# ProtectionChannelB.net
KiCad netlist of a schematic drawn in Altium Designer
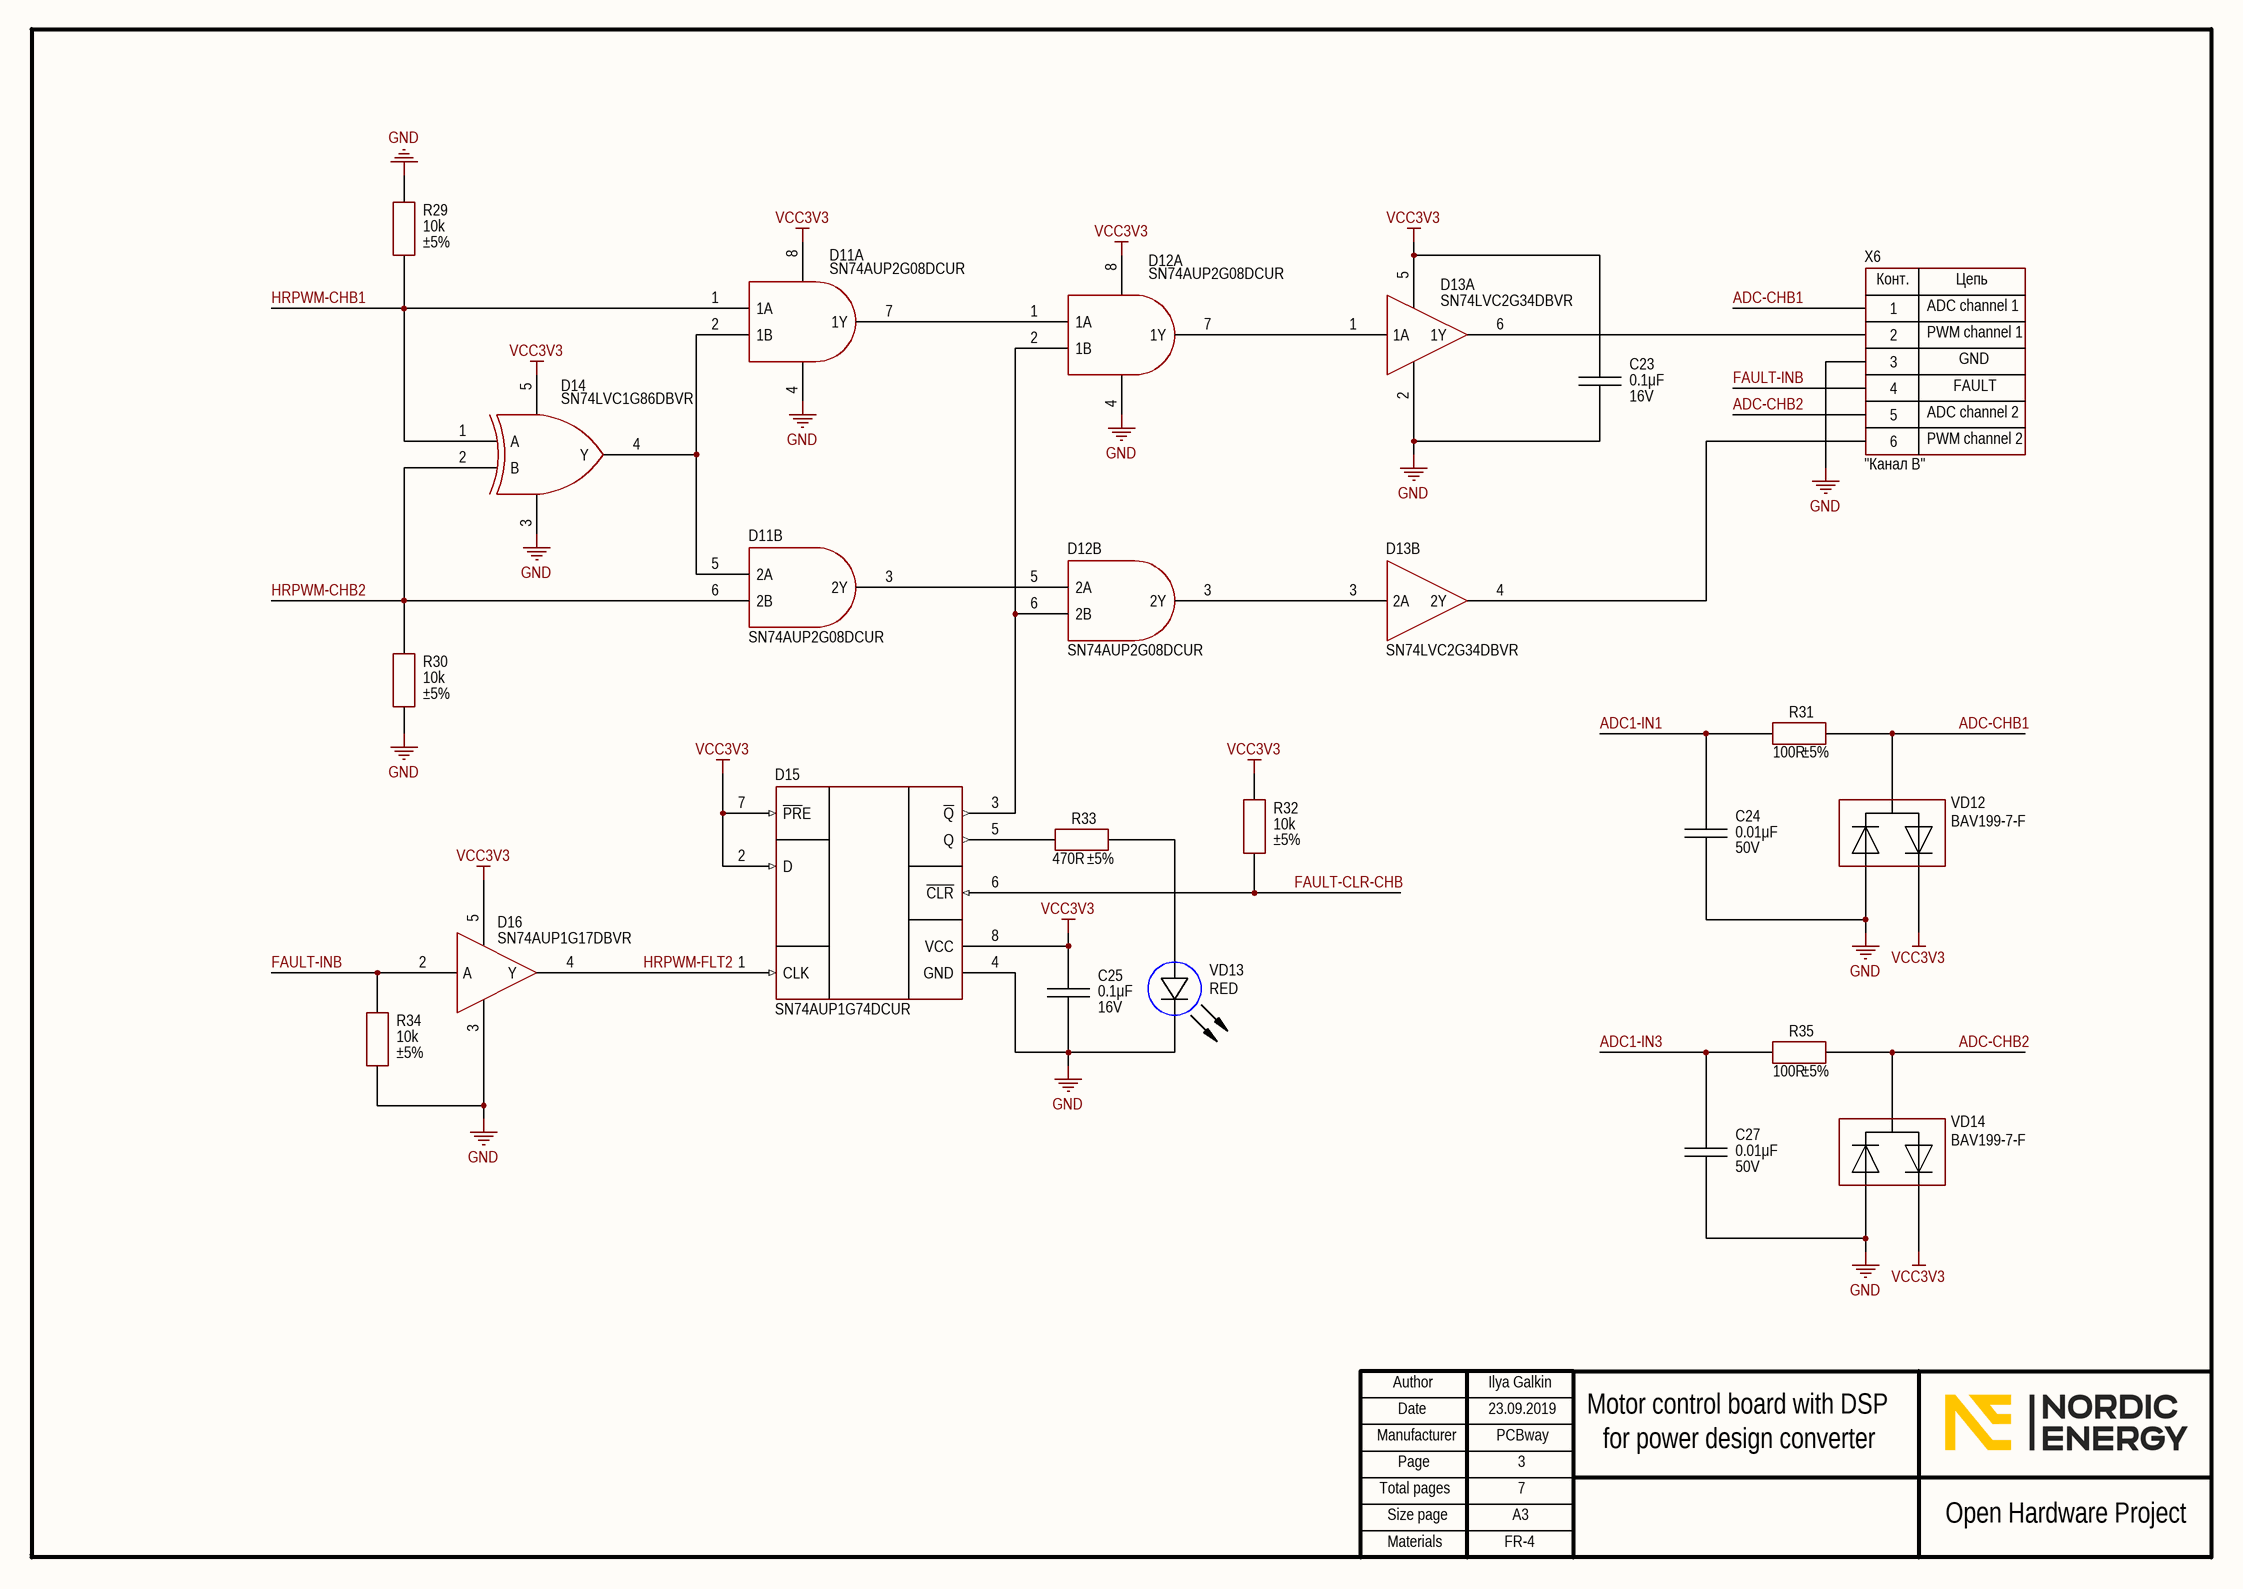
[diagram p0: ProtectionChannelB.SchDoc]

(export (version "E")
  (design (tool "Eeschema 10.0.6"))
  (components
    (comp (ref "C23")
      (value "0.1μF")
      (footprint "CAP: 0805")
      (fields
        (field (name "MANUFACTURER") "Yageo")
        (field (name "PARTNUMBER") "CC0805KRX7R7BB104")
        (field (name "VALUEMANUFACTURERPARTNUMBER") "Ceramic capacitor, 0.1μF, X7R, ±10%, 16V, 0805, -55...+125°C")
        (field (name "VOLTAGE") "16V")
      )
      (libsource (lib "Capacitor") (part "Ceramic_0805"))
    )
    (comp (ref "C24")
      (value "0.01μF")
      (footprint "CAP: 0805")
      (fields
        (field (name "MANUFACTURER") "Yageo")
        (field (name "PARTNUMBER") "CC0805KRX7R9BB103")
        (field (name "VALUEMANUFACTURERPARTNUMBER") "Ceramic capacitor, 0.01μF, X7R, ±10%, 50V, 0805, -55...+125°C")
        (field (name "VOLTAGE") "50V")
      )
      (libsource (lib "Capacitor") (part "Ceramic_0805"))
    )
    (comp (ref "C25")
      (value "0.1μF")
      (footprint "CAP: 0805")
      (fields
        (field (name "MANUFACTURER") "Yageo")
        (field (name "PARTNUMBER") "CC0805KRX7R7BB104")
        (field (name "VALUEMANUFACTURERPARTNUMBER") "Ceramic capacitor, 0.1μF, X7R, ±10%, 16V, 0805, -55...+125°C")
        (field (name "VOLTAGE") "16V")
      )
      (libsource (lib "Capacitor") (part "Ceramic_0805"))
    )
    (comp (ref "C27")
      (value "0.01μF")
      (footprint "CAP: 0805")
      (fields
        (field (name "MANUFACTURER") "Yageo")
        (field (name "PARTNUMBER") "CC0805KRX7R9BB103")
        (field (name "VALUEMANUFACTURERPARTNUMBER") "Ceramic capacitor, 0.01μF, X7R, ±10%, 50V, 0805, -55...+125°C")
        (field (name "VOLTAGE") "50V")
      )
      (libsource (lib "Capacitor") (part "Ceramic_0805"))
    )
    (comp (ref "D11")
      (value "~")
      (footprint "8-VSSOP")
      (description "AND")
      (fields
        (field (name "MANUFACTURER") "Texas Instruments")
        (field (name "VALUEMANUFACTURERPARTNUMBER") "IC logic AND, 0.8...3.6V, -40...+855°C, 8-VSSOP")
        (field (name "PARTNUMBER") "SN74AUP2G08DCUR")
      )
      (libsource (lib "IC. Logic") (part "SN74AUP2G08DCUR"))
    )
    (comp (ref "D12")
      (value "~")
      (footprint "8-VSSOP")
      (description "AND")
      (fields
        (field (name "MANUFACTURER") "Texas Instruments")
        (field (name "VALUEMANUFACTURERPARTNUMBER") "IC logic AND, 0.8...3.6V, -40...+855°C, 8-VSSOP")
        (field (name "PARTNUMBER") "SN74AUP2G08DCUR")
      )
      (libsource (lib "IC. Logic") (part "SN74AUP2G08DCUR"))
    )
    (comp (ref "D13")
      (value "~")
      (footprint "SOT23-6")
      (description "Buffer")
      (fields
        (field (name "MANUFACTURER") "Texas Instruments")
        (field (name "VALUEMANUFACTURERPARTNUMBER") "IC logic buffer, 1.65...5.5V, -40...+125°C, SOT23-6")
        (field (name "PARTNUMBER") "SN74LVC2G34DBVR")
      )
      (libsource (lib "IC. Logic") (part "SN74LVC2G34DBVR"))
    )
    (comp (ref "D14")
      (value "~")
      (footprint "SOT23-5")
      (description "XOR")
      (fields
        (field (name "MANUFACTURER") "Texas Instruments")
        (field (name "VALUEMANUFACTURERPARTNUMBER") "IC logic XOR, 1.65...5.5V, -40...+125°C, SOT23-5")
        (field (name "PARTNUMBER") "SN74LVC1G86DBVR")
      )
      (libsource (lib "IC. Logic") (part "SN74LVC1G86DBVR"))
    )
    (comp (ref "D15")
      (value "~")
      (footprint "8-VSSOP")
      (description "D-trigger")
      (fields
        (field (name "MANUFACTURER") "Texas Instruments")
        (field (name "VALUEMANUFACTURERPARTNUMBER") "ICtrigger D-type, 0.8...3.6V, -40...+85°C, 8-VSSOP")
        (field (name "PARTNUMBER") "SN74AUP1G74DCUR")
      )
      (libsource (lib "IC. Logic") (part "SN74AUP1G74DCUR"))
    )
    (comp (ref "D16")
      (value "~")
      (footprint "SOT23-5")
      (description "Schmitt trigger")
      (fields
        (field (name "MANUFACTURER") "Texas Instruments")
        (field (name "VALUEMANUFACTURERPARTNUMBER") "IC Schmitt trigger, 0.8...3.6V, -40...+85°C, SOT23-6")
        (field (name "PARTNUMBER") "SN74AUP1G17DBVR")
      )
      (libsource (lib "IC. Logic") (part "SN74AUP1G17DBVR"))
    )
    (comp (ref "R29")
      (value "10k")
      (footprint "RES: 0805")
      (fields
        (field (name "MANUFACTURER") "Yageo")
        (field (name "PARTNUMBER") "RC0805JR-0710KL")
        (field (name "VALUEMANUFACTURERPARTNUMBER") "Resistor film, 10k, ±5%, 0805, 0.125W, -55...+125°C")
        (field (name "TOLERANCE") "±5%")
      )
      (libsource (lib "") (part "Resistor_0805_1"))
    )
    (comp (ref "R30")
      (value "10k")
      (footprint "RES: 0805")
      (fields
        (field (name "MANUFACTURER") "Yageo")
        (field (name "PARTNUMBER") "RC0805JR-0710KL")
        (field (name "VALUEMANUFACTURERPARTNUMBER") "Resistor film, 10k, ±5%, 0805, 0.125W, -55...+125°C")
        (field (name "TOLERANCE") "±5%")
      )
      (libsource (lib "") (part "Resistor_0805_1"))
    )
    (comp (ref "R31")
      (value "100R")
      (footprint "RES: 0805")
      (fields
        (field (name "MANUFACTURER") "Yageo")
        (field (name "PARTNUMBER") "RC0805JR-07100RL")
        (field (name "VALUEMANUFACTURERPARTNUMBER") "Resistor film, 100R, ±5%, 0805, 0.125W, -55...+125°C")
        (field (name "TOLERANCE") "±5%")
      )
      (libsource (lib "Resistor") (part "Resistor_0805"))
    )
    (comp (ref "R32")
      (value "10k")
      (footprint "RES: 0805")
      (fields
        (field (name "MANUFACTURER") "Yageo")
        (field (name "PARTNUMBER") "RC0805JR-0710KL")
        (field (name "VALUEMANUFACTURERPARTNUMBER") "Resistor film, 10k, ±5%, 0805, 0.125W, -55...+125°C")
        (field (name "TOLERANCE") "±5%")
      )
      (libsource (lib "") (part "Resistor_0805_1"))
    )
    (comp (ref "R33")
      (value "470R")
      (footprint "RES: 0805")
      (fields
        (field (name "MANUFACTURER") "Yageo")
        (field (name "PARTNUMBER") "RC0805JR-07470RL")
        (field (name "VALUEMANUFACTURERPARTNUMBER") "Resistor film, 470R, ±5%, 0805, 0.125W, -55...+125°C")
        (field (name "TOLERANCE") "±5%")
      )
      (libsource (lib "") (part "Resistor_0805_2"))
    )
    (comp (ref "R34")
      (value "10k")
      (footprint "RES: 0805")
      (fields
        (field (name "MANUFACTURER") "Yageo")
        (field (name "PARTNUMBER") "RC0805JR-0710KL")
        (field (name "VALUEMANUFACTURERPARTNUMBER") "Resistor film, 10k, ±5%, 0805, 0.125W, -55...+125°C")
        (field (name "TOLERANCE") "±5%")
      )
      (libsource (lib "") (part "Resistor_0805_1"))
    )
    (comp (ref "R35")
      (value "100R")
      (footprint "RES: 0805")
      (fields
        (field (name "MANUFACTURER") "Yageo")
        (field (name "PARTNUMBER") "RC0805JR-07100RL")
        (field (name "VALUEMANUFACTURERPARTNUMBER") "Resistor film, 100R, ±5%, 0805, 0.125W, -55...+125°C")
        (field (name "TOLERANCE") "±5%")
      )
      (libsource (lib "Resistor") (part "Resistor_0805"))
    )
    (comp (ref "VD12")
      (value "~")
      (footprint "SOT23")
      (fields
        (field (name "MANUFACTURER") "Diodes Incorporated")
        (field (name "VALUEMANUFACTURERPARTNUMBER") "Diode array, 85V, 140mA, 1.1V, 3us, SOT-23, -65...+150°C")
        (field (name "VOLTAGE") "85V")
        (field (name "PARTNUMBER") "BAV199-7-F")
      )
      (libsource (lib "Diode") (part "Diode_array"))
    )
    (comp (ref "VD13")
      (value "~")
      (footprint "LED: 0805R")
      (fields
        (field (name "MANUFACTURER") "Wurth")
        (field (name "VALUEMANUFACTURERPARTNUMBER") "LED, 20mA, 2V, 0805, -55...+150°C")
        (field (name "PARTNUMBER") "150080RS75000")
        (field (name "COLOR") "RED")
      )
      (libsource (lib "Diode") (part "LED_single"))
    )
    (comp (ref "VD14")
      (value "~")
      (footprint "SOT23")
      (fields
        (field (name "MANUFACTURER") "Diodes Incorporated")
        (field (name "VALUEMANUFACTURERPARTNUMBER") "Diode array, 85V, 140mA, 1.1V, 3us, SOT-23, -65...+150°C")
        (field (name "VOLTAGE") "85V")
        (field (name "PARTNUMBER") "BAV199-7-F")
      )
      (libsource (lib "Diode") (part "Diode_array"))
    )
    (comp (ref "X6")
      (value "~")
      (footprint "CON: PLD-6")
      (fields
        (field (name "MANUFACTURER") "Connfly")
        (field (name "VALUEMANUFACTURERPARTNUMBER") "Connector, 6pin, 2.54mm, 500VAC, 3A")
        (field (name "PARTNUMBER") "PLD-6")
        (field (name "COMMENTTEXT") "\"Канал B\"")
      )
      (libsource (lib "Connector") (part "PLD-6"))
    )
  )
  (nets
    (net (code "1") (name "/ADC-CHB1") (class "Default")
      (node (ref "R31") (pin "2") (pinfunction "2_2") (pintype "passive"))
      (node (ref "VD12") (pin "3") (pinfunction "3_3") (pintype "passive"))
      (node (ref "X6") (pin "1") (pinfunction "1_1") (pintype "passive"))
    )
    (net (code "2") (name "/ADC-CHB2") (class "Default")
      (node (ref "R35") (pin "2") (pinfunction "2_2") (pintype "passive"))
      (node (ref "VD14") (pin "3") (pinfunction "3_3") (pintype "passive"))
      (node (ref "X6") (pin "5") (pinfunction "5_5") (pintype "power_in"))
    )
    (net (code "3") (name "/ADC1-IN1") (class "Default")
      (node (ref "C24") (pin "2") (pinfunction "2_2") (pintype "power_in"))
      (node (ref "R31") (pin "1") (pinfunction "1_1") (pintype "passive"))
    )
    (net (code "4") (name "/ADC1-IN3") (class "Default")
      (node (ref "C27") (pin "2") (pinfunction "2_2") (pintype "power_in"))
      (node (ref "R35") (pin "1") (pinfunction "1_1") (pintype "passive"))
    )
    (net (code "5") (name "/FAULT-CLR-CHB") (class "Default")
      (node (ref "D15") (pin "6") (pinfunction "~{CLR}_6") (pintype "input"))
      (node (ref "R32") (pin "2") (pinfunction "2_2") (pintype "passive"))
    )
    (net (code "6") (name "/FAULT-INB") (class "Default")
      (node (ref "D16") (pin "2") (pinfunction "A_2") (pintype "passive"))
      (node (ref "R34") (pin "1") (pinfunction "1_1") (pintype "passive"))
      (node (ref "X6") (pin "4") (pinfunction "4_4") (pintype "power_in"))
    )
    (net (code "7") (name "/HRPWM-CHB1") (class "Default")
      (node (ref "D11") (pin "1") (pinfunction "1A_1") (pintype "passive"))
      (node (ref "D14") (pin "1") (pinfunction "A_1") (pintype "passive"))
      (node (ref "R29") (pin "2") (pinfunction "2_2") (pintype "passive"))
    )
    (net (code "8") (name "/HRPWM-CHB2") (class "Default")
      (node (ref "D11") (pin "6") (pinfunction "2B_6") (pintype "passive"))
      (node (ref "D14") (pin "2") (pinfunction "B_2") (pintype "passive"))
      (node (ref "R30") (pin "1") (pinfunction "1_1") (pintype "passive"))
    )
    (net (code "9") (name "/HRPWM-FLT2") (class "Default")
      (node (ref "D15") (pin "1") (pinfunction "CLK_1") (pintype "input"))
      (node (ref "D16") (pin "4") (pinfunction "Y_4") (pintype "passive"))
    )
    (net (code "10") (name "GND") (class "Default")
      (node (ref "C23") (pin "1") (pinfunction "1_1") (pintype "power_in"))
      (node (ref "C24") (pin "1") (pinfunction "1_1") (pintype "power_in"))
      (node (ref "C25") (pin "1") (pinfunction "1_1") (pintype "power_in"))
      (node (ref "C27") (pin "1") (pinfunction "1_1") (pintype "power_in"))
      (node (ref "D11") (pin "4") (pintype "passive"))
      (node (ref "D12") (pin "4") (pintype "passive"))
      (node (ref "D13") (pin "2") (pintype "passive"))
      (node (ref "D14") (pin "3") (pintype "passive"))
      (node (ref "D15") (pin "4") (pinfunction "GND_4") (pintype "passive"))
      (node (ref "D16") (pin "3") (pintype "passive"))
      (node (ref "R29") (pin "1") (pinfunction "1_1") (pintype "passive"))
      (node (ref "R30") (pin "2") (pinfunction "2_2") (pintype "passive"))
      (node (ref "R34") (pin "2") (pinfunction "2_2") (pintype "passive"))
      (node (ref "VD12") (pin "1") (pinfunction "1_1") (pintype "passive"))
      (node (ref "VD13") (pin "2") (pinfunction "C_2") (pintype "passive"))
      (node (ref "VD14") (pin "1") (pinfunction "1_1") (pintype "passive"))
      (node (ref "X6") (pin "3") (pinfunction "3_3") (pintype "power_in"))
    )
    (net (code "11") (name "Net-(D11A-1B)") (class "Default")
      (node (ref "D11") (pin "2") (pinfunction "1B_2") (pintype "passive"))
      (node (ref "D11") (pin "5") (pinfunction "2A_5") (pintype "passive"))
      (node (ref "D14") (pin "4") (pinfunction "Y_4") (pintype "passive"))
    )
    (net (code "12") (name "Net-(D11A-1Y)") (class "Default")
      (node (ref "D11") (pin "7") (pinfunction "1Y_7") (pintype "passive"))
      (node (ref "D12") (pin "1") (pinfunction "1A_1") (pintype "passive"))
    )
    (net (code "13") (name "Net-(D11B-2Y)") (class "Default")
      (node (ref "D11") (pin "3") (pinfunction "2Y_3") (pintype "passive"))
      (node (ref "D12") (pin "5") (pinfunction "2A_5") (pintype "passive"))
    )
    (net (code "14") (name "Net-(D12A-1B)") (class "Default")
      (node (ref "D12") (pin "2") (pinfunction "1B_2") (pintype "passive"))
      (node (ref "D12") (pin "6") (pinfunction "2B_6") (pintype "passive"))
      (node (ref "D15") (pin "3") (pinfunction "~{Q}_3") (pintype "output"))
    )
    (net (code "15") (name "Net-(D12A-1Y)") (class "Default")
      (node (ref "D12") (pin "7") (pinfunction "1Y_7") (pintype "passive"))
      (node (ref "D13") (pin "1") (pinfunction "1A_1") (pintype "passive"))
    )
    (net (code "16") (name "Net-(D12B-2Y)") (class "Default")
      (node (ref "D12") (pin "3") (pinfunction "2Y_3") (pintype "passive"))
      (node (ref "D13") (pin "3") (pinfunction "2A_3") (pintype "passive"))
    )
    (net (code "17") (name "Net-(D13A-1Y)") (class "Default")
      (node (ref "D13") (pin "6") (pinfunction "1Y_6") (pintype "passive"))
      (node (ref "X6") (pin "2") (pinfunction "2_2") (pintype "passive"))
    )
    (net (code "18") (name "Net-(D13B-2Y)") (class "Default")
      (node (ref "D13") (pin "4") (pinfunction "2Y_4") (pintype "passive"))
      (node (ref "X6") (pin "6") (pinfunction "6_6") (pintype "power_in"))
    )
    (net (code "19") (name "Net-(D15-Q)") (class "Default")
      (node (ref "D15") (pin "5") (pinfunction "Q_5") (pintype "output"))
      (node (ref "R33") (pin "2") (pinfunction "2_2") (pintype "passive"))
    )
    (net (code "20") (name "Net-(VD13-A)") (class "Default")
      (node (ref "R33") (pin "1") (pinfunction "1_1") (pintype "passive"))
      (node (ref "VD13") (pin "1") (pinfunction "A_1") (pintype "passive"))
    )
    (net (code "21") (name "VCC3V3") (class "Default")
      (node (ref "C23") (pin "2") (pinfunction "2_2") (pintype "power_in"))
      (node (ref "C25") (pin "2") (pinfunction "2_2") (pintype "power_in"))
      (node (ref "D11") (pin "8") (pintype "passive"))
      (node (ref "D12") (pin "8") (pintype "passive"))
      (node (ref "D13") (pin "5") (pintype "passive"))
      (node (ref "D14") (pin "5") (pintype "passive"))
      (node (ref "D15") (pin "2") (pinfunction "D_2") (pintype "input"))
      (node (ref "D15") (pin "7") (pinfunction "~{PR}E_7") (pintype "input"))
      (node (ref "D15") (pin "8") (pinfunction "VCC_8") (pintype "passive"))
      (node (ref "D16") (pin "5") (pintype "passive"))
      (node (ref "R32") (pin "1") (pinfunction "1_1") (pintype "passive"))
      (node (ref "VD12") (pin "2") (pinfunction "2_2") (pintype "passive"))
      (node (ref "VD14") (pin "2") (pinfunction "2_2") (pintype "passive"))
    )
  )
)
